# 1-Schematic_LoPoSwitch.net
KiCad netlist of a schematic drawn in EasyEDA
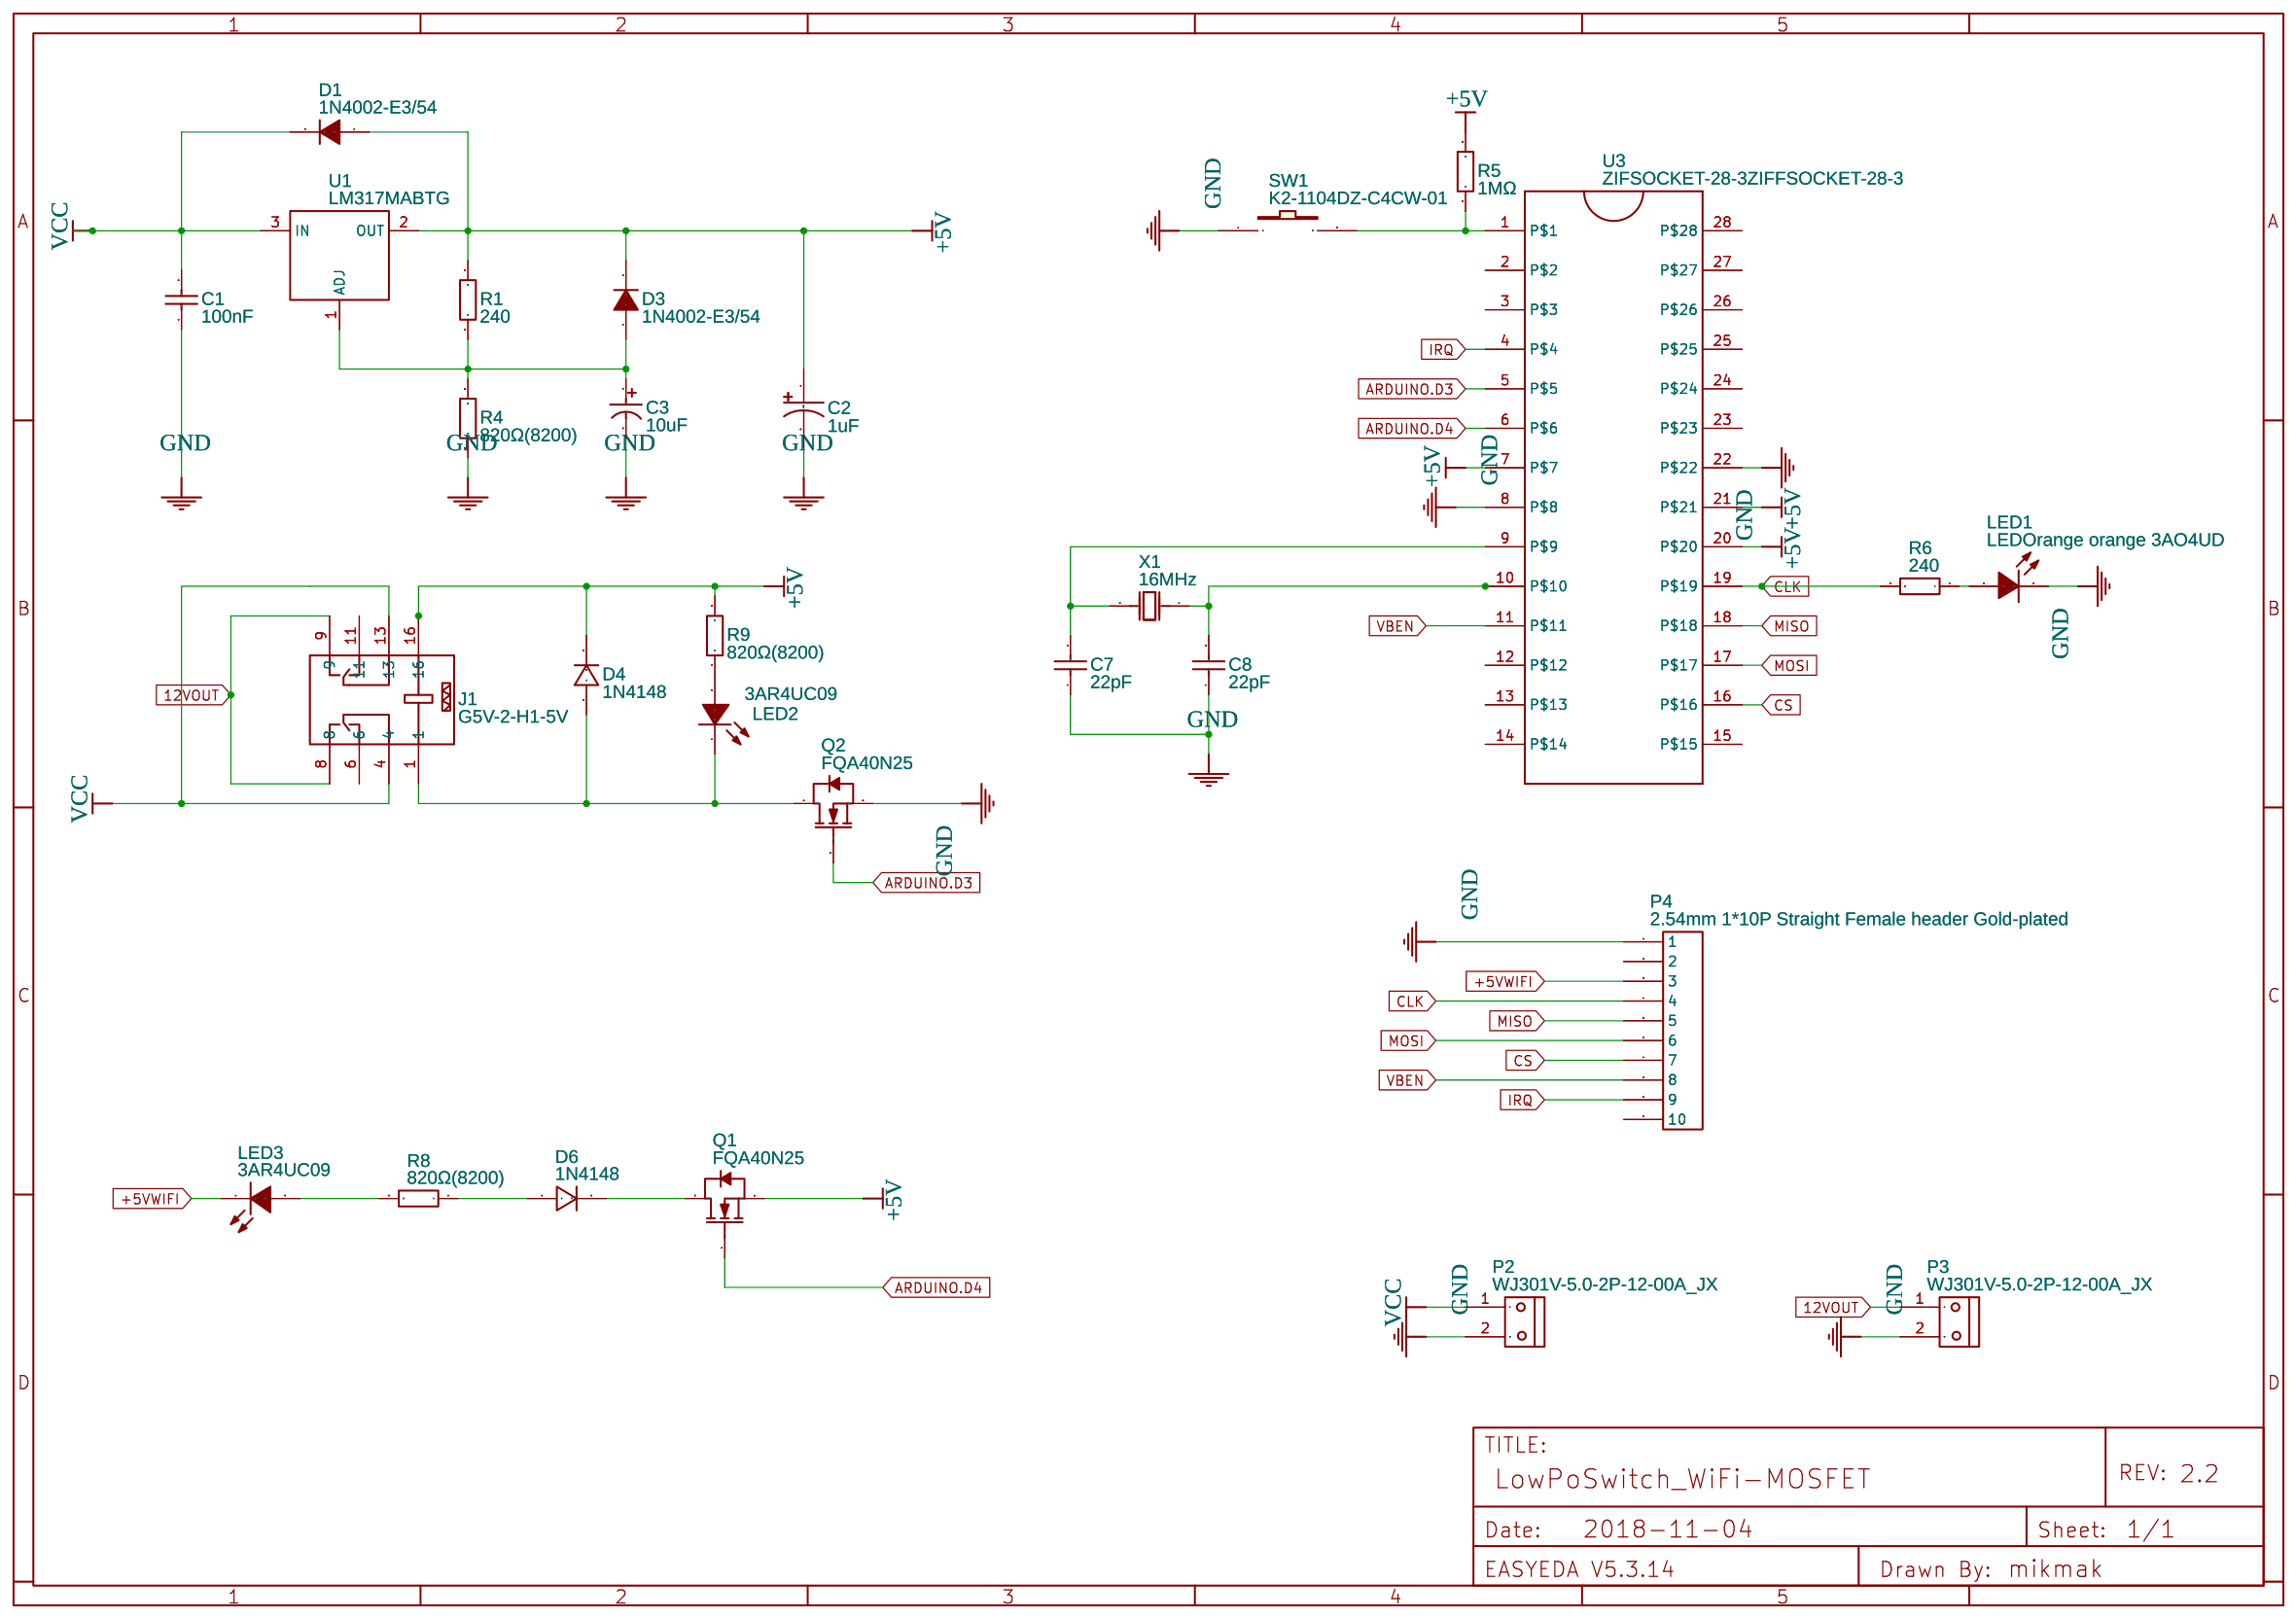
[diagram p0: schematic sheet]

(export (version "E")
  (design (tool "Eeschema 10.0.6"))
  (components
    (comp (ref "C1")
      (value "100nF")
      (fields
        (field (name "BOM_Manufacturer Part") "MPP104K5130508LC")
        (field (name "BOM_Supplier Part") "C109523")
      )
      (libsource (lib "") (part "MPP104K5130508LC"))
    )
    (comp (ref "C2")
      (value "1uF")
      (fields
        (field (name "BOM_Manufacturer Part") "T322A105K020AT")
        (field (name "BOM_Supplier Part") "C219517")
      )
      (libsource (lib "") (part "T322A105K020AT"))
    )
    (comp (ref "C3")
      (value "10uF")
      (fields (field (name "BOM_Manufacturer Part") "10uf/100V") (field (name "BOM_Supplier Part") "C2029"))
      (libsource (lib "") (part "10uf/100V"))
    )
    (comp (ref "C7")
      (value "22pF")
      (fields
        (field (name "BOM_Manufacturer Part") "Monolithic0603N220J500")
        (field (name "BOM_Supplier Part") "C110283")
      )
      (libsource (lib "") (part "Monolithic0603N220J500"))
    )
    (comp (ref "C8")
      (value "22pF")
      (fields
        (field (name "BOM_Manufacturer Part") "Monolithic0603N220J500")
        (field (name "BOM_Supplier Part") "C110283")
      )
      (libsource (lib "") (part "Monolithic0603N220J500"))
    )
    (comp (ref "D1")
      (value "1N4002-E3/54")
      (fields (field (name "BOM_Supplier Part") "C33504"))
      (libsource (lib "") (part "Unknown_160_60"))
    )
    (comp (ref "D3")
      (value "1N4002-E3/54")
      (fields (field (name "BOM_Supplier Part") "C33504"))
      (libsource (lib "") (part "Unknown_310_145"))
    )
    (comp (ref "D4")
      (value "1N4148")
      (fields (field (name "BOM_Supplier Part") "C163750"))
      (libsource (lib "") (part "Unknown_290_335"))
    )
    (comp (ref "D6")
      (value "1N4148")
      (fields (field (name "BOM_Supplier Part") "C163750"))
      (libsource (lib "") (part "Unknown_280_600"))
    )
    (comp (ref "J1")
      (value "G5V-2-H1-5V")
      (fields (field (name "BOM_Supplier Part") "C28066"))
      (libsource (lib "") (part "Unknown_185_340"))
    )
    (comp (ref "LED1")
      (value "LEDOrange orange 3AO4UD")
      (fields (field (name "BOM_Supplier Part") "C62095"))
      (libsource (lib "") (part "Unknown_1010_290"))
    )
    (comp (ref "LED2")
      (value "3AR4UC09")
      (fields (field (name "BOM_Supplier Part") "C6211"))
      (libsource (lib "") (part "Unknown_355_355"))
    )
    (comp (ref "LED3")
      (value "3AR4UC09")
      (fields (field (name "BOM_Supplier Part") "C6211"))
      (libsource (lib "") (part "Unknown_125_600"))
    )
    (comp (ref "P2")
      (value "WJ301V-5.0-2P-12-00A_JX")
      (fields (field (name "BOM_Manufacturer Part") "?") (field (name "BOM_Supplier Part") "C72326"))
      (libsource (lib "") (part "Unknown_755_655"))
    )
    (comp (ref "P3")
      (value "WJ301V-5.0-2P-12-00A_JX")
      (fields (field (name "BOM_Manufacturer Part") "?") (field (name "BOM_Supplier Part") "C72326"))
      (libsource (lib "") (part "Unknown_975_655"))
    )
    (comp (ref "P4")
      (value "2.54mm 1*10P Straight Female header Gold-plated")
      (fields (field (name "BOM_Supplier Part") "C35445"))
      (libsource (lib "") (part "Unknown_825_510"))
    )
    (comp (ref "Q1")
      (value "FQA40N25")
      (fields (field (name "BOM_Supplier Part") "C10877"))
      (libsource (lib "") (part "Unknown_360_610"))
    )
    (comp (ref "Q2")
      (value "FQA40N25")
      (fields (field (name "BOM_Supplier Part") "C10877"))
      (libsource (lib "") (part "Unknown_415_410"))
    )
    (comp (ref "R1")
      (value "240")
      (fields
        (field (name "BOM_Manufacturer Part") "MF1/8W-240Ω±1% T52")
        (field (name "BOM_Supplier Part") "C119165")
      )
      (libsource (lib "") (part "MF1/8W-240Ω±1% T52"))
    )
    (comp (ref "R4")
      (value "820Ω(8200)")
      (fields
        (field (name "BOM_Manufacturer Part") "MF1/8W-820Ω±1% T52")
        (field (name "BOM_Supplier Part") "C119177")
      )
      (libsource (lib "") (part "MF1/8W-820Ω±1% T52"))
    )
    (comp (ref "R5")
      (value "1MΩ")
      (fields
        (field (name "BOM_Manufacturer Part") "MFR0W4F1004A50")
        (field (name "BOM_Supplier Part") "C58596")
      )
      (libsource (lib "") (part "MFR0W4F1004A50"))
    )
    (comp (ref "R6")
      (value "240")
      (fields
        (field (name "BOM_Manufacturer Part") "MF1/8W-240Ω±1% T52")
        (field (name "BOM_Supplier Part") "C119165")
      )
      (libsource (lib "") (part "MF1/8W-240Ω±1% T52_1"))
    )
    (comp (ref "R8")
      (value "820Ω(8200)")
      (fields
        (field (name "BOM_Manufacturer Part") "MF1/8W-820Ω±1% T52")
        (field (name "BOM_Supplier Part") "C119177")
      )
      (libsource (lib "") (part "MF1/8W-820Ω±1% T52_1"))
    )
    (comp (ref "R9")
      (value "820Ω(8200)")
      (fields
        (field (name "BOM_Manufacturer Part") "MF1/8W-820Ω±1% T52")
        (field (name "BOM_Supplier Part") "C119177")
      )
      (libsource (lib "") (part "MF1/8W-820Ω±1% T52"))
    )
    (comp (ref "SW1")
      (value "K2-1104DZ-C4CW-01")
      (fields (field (name "BOM_Supplier Part") "C145889"))
      (libsource (lib "") (part "Unknown_640_110"))
    )
    (comp (ref "U1")
      (value "LM317MABTG")
      (fields (field (name "BOM_Supplier Part") "C94823"))
      (libsource (lib "") (part "Unknown_165_120"))
    )
    (comp (ref "U3")
      (value "ZIFSOCKET-28-3ZIFFSOCKET-28-3")
      (fields (field (name "BOM_Manufacturer Part") "?"))
      (libsource (lib "") (part "Unknown_765_390"))
    )
    (comp (ref "X1")
      (value "16MHz")
      (fields
        (field (name "BOM_Manufacturer Part") "X49SD16MSD2SC")
        (field (name "BOM_Supplier Part") "C16212")
      )
      (libsource (lib "") (part "X49SD16MSD2SC"))
    )
  )
  (nets
    (net (code "1") (name "+5V") (class "Default")
      (node (ref "C2") (pin "1") (pinfunction "1_1") (pintype "unspecified"))
      (node (ref "D1") (pin "1") (pinfunction "A_1") (pintype "unspecified"))
      (node (ref "D3") (pin "2") (pinfunction "K_2") (pintype "unspecified"))
      (node (ref "D4") (pin "2") (pinfunction "2_2") (pintype "unspecified"))
      (node (ref "J1") (pin "16") (pinfunction "16_16") (pintype "unspecified"))
      (node (ref "Q1") (pin "3") (pinfunction "S_3") (pintype "unspecified"))
      (node (ref "R1") (pin "2") (pinfunction "2_2") (pintype "input"))
      (node (ref "R5") (pin "2") (pinfunction "2_2") (pintype "input"))
      (node (ref "R9") (pin "2") (pinfunction "2_2") (pintype "input"))
      (node (ref "U1") (pin "2") (pinfunction "OUT_2") (pintype "unspecified"))
      (node (ref "U3") (pin "20") (pinfunction "P$20_20") (pintype "unspecified"))
      (node (ref "U3") (pin "21") (pinfunction "P$21_21") (pintype "unspecified"))
      (node (ref "U3") (pin "7") (pinfunction "P$7_7") (pintype "unspecified"))
    )
    (net (code "2") (name "+5VWIFI") (class "Default")
      (node (ref "LED3") (pin "1") (pinfunction "K_1") (pintype "unspecified"))
      (node (ref "P4") (pin "3") (pinfunction "3_3") (pintype "input"))
    )
    (net (code "3") (name "12VOUT") (class "Default")
      (node (ref "J1") (pin "8") (pinfunction "8_8") (pintype "unspecified"))
      (node (ref "J1") (pin "9") (pinfunction "9_9") (pintype "unspecified"))
      (node (ref "P3") (pin "1") (pinfunction "1_1") (pintype "unspecified"))
    )
    (net (code "4") (name "ARDUINO.D3") (class "Default")
      (node (ref "Q2") (pin "1") (pinfunction "G_1") (pintype "unspecified"))
      (node (ref "U3") (pin "5") (pinfunction "P$5_5") (pintype "unspecified"))
    )
    (net (code "5") (name "ARDUINO.D4") (class "Default")
      (node (ref "Q1") (pin "1") (pinfunction "G_1") (pintype "unspecified"))
      (node (ref "U3") (pin "6") (pinfunction "P$6_6") (pintype "unspecified"))
    )
    (net (code "6") (name "CLK") (class "Default")
      (node (ref "P4") (pin "4") (pinfunction "4_4") (pintype "input"))
      (node (ref "R6") (pin "2") (pinfunction "2_2") (pintype "input"))
      (node (ref "U3") (pin "19") (pinfunction "P$19_19") (pintype "unspecified"))
    )
    (net (code "7") (name "CS") (class "Default")
      (node (ref "P4") (pin "7") (pinfunction "7_7") (pintype "input"))
      (node (ref "U3") (pin "16") (pinfunction "P$16_16") (pintype "unspecified"))
    )
    (net (code "8") (name "GND") (class "Default")
      (node (ref "C1") (pin "1") (pinfunction "1_1") (pintype "input"))
      (node (ref "C2") (pin "2") (pinfunction "2_2") (pintype "unspecified"))
      (node (ref "C3") (pin "2") (pinfunction "2_2") (pintype "input"))
      (node (ref "C7") (pin "1") (pinfunction "1_1") (pintype "input"))
      (node (ref "C8") (pin "1") (pinfunction "1_1") (pintype "input"))
      (node (ref "LED1") (pin "1") (pinfunction "K_1") (pintype "unspecified"))
      (node (ref "P2") (pin "2") (pinfunction "2_2") (pintype "unspecified"))
      (node (ref "P3") (pin "2") (pinfunction "2_2") (pintype "unspecified"))
      (node (ref "P4") (pin "1") (pinfunction "1_1") (pintype "input"))
      (node (ref "Q2") (pin "3") (pinfunction "S_3") (pintype "unspecified"))
      (node (ref "R4") (pin "1") (pinfunction "1_1") (pintype "input"))
      (node (ref "SW1") (pin "1") (pinfunction "1_1") (pintype "input"))
      (node (ref "U3") (pin "22") (pinfunction "P$22_22") (pintype "unspecified"))
      (node (ref "U3") (pin "8") (pinfunction "P$8_8") (pintype "unspecified"))
    )
    (net (code "9") (name "IRQ") (class "Default")
      (node (ref "P4") (pin "9") (pinfunction "9_9") (pintype "input"))
      (node (ref "U3") (pin "4") (pinfunction "P$4_4") (pintype "unspecified"))
    )
    (net (code "10") (name "MISO") (class "Default")
      (node (ref "P4") (pin "5") (pinfunction "5_5") (pintype "input"))
      (node (ref "U3") (pin "18") (pinfunction "P$18_18") (pintype "unspecified"))
    )
    (net (code "11") (name "MOSI") (class "Default")
      (node (ref "P4") (pin "6") (pinfunction "6_6") (pintype "input"))
      (node (ref "U3") (pin "17") (pinfunction "P$17_17") (pintype "unspecified"))
    )
    (net (code "12") (name "Net-(D3-A)") (class "Default")
      (node (ref "C3") (pin "1") (pinfunction "1_1") (pintype "input"))
      (node (ref "D3") (pin "1") (pinfunction "A_1") (pintype "unspecified"))
      (node (ref "R1") (pin "1") (pinfunction "1_1") (pintype "input"))
      (node (ref "R4") (pin "2") (pinfunction "2_2") (pintype "input"))
      (node (ref "U1") (pin "1") (pinfunction "ADJ_1") (pintype "input"))
    )
    (net (code "13") (name "Net-(D6-Pad1)") (class "Default")
      (node (ref "D6") (pin "1") (pinfunction "1_1") (pintype "unspecified"))
      (node (ref "R8") (pin "1") (pinfunction "1_1") (pintype "input"))
    )
    (net (code "14") (name "Net-(LED1-A)") (class "Default")
      (node (ref "LED1") (pin "2") (pinfunction "A_2") (pintype "unspecified"))
      (node (ref "R6") (pin "1") (pinfunction "1_1") (pintype "input"))
    )
    (net (code "15") (name "Net-(LED2-A)") (class "Default")
      (node (ref "LED2") (pin "2") (pinfunction "A_2") (pintype "unspecified"))
      (node (ref "R9") (pin "1") (pinfunction "1_1") (pintype "input"))
    )
    (net (code "16") (name "Net-(LED2-K)") (class "Default")
      (node (ref "D4") (pin "1") (pinfunction "1_1") (pintype "unspecified"))
      (node (ref "J1") (pin "1") (pinfunction "1_1") (pintype "unspecified"))
      (node (ref "LED2") (pin "1") (pinfunction "K_1") (pintype "unspecified"))
      (node (ref "Q2") (pin "2") (pinfunction "D_2") (pintype "unspecified"))
    )
    (net (code "17") (name "Net-(LED3-A)") (class "Default")
      (node (ref "LED3") (pin "2") (pinfunction "A_2") (pintype "unspecified"))
      (node (ref "R8") (pin "2") (pinfunction "2_2") (pintype "input"))
    )
    (net (code "18") (name "Net-(Q1-D)") (class "Default")
      (node (ref "D6") (pin "2") (pinfunction "2_2") (pintype "unspecified"))
      (node (ref "Q1") (pin "2") (pinfunction "D_2") (pintype "unspecified"))
    )
    (net (code "19") (name "Net-(U3-P$1)") (class "Default")
      (node (ref "R5") (pin "1") (pinfunction "1_1") (pintype "input"))
      (node (ref "SW1") (pin "2") (pinfunction "2_2") (pintype "input"))
      (node (ref "U3") (pin "1") (pinfunction "P$1_1") (pintype "unspecified"))
    )
    (net (code "20") (name "Net-(U3-P$9)") (class "Default")
      (node (ref "C7") (pin "2") (pinfunction "2_2") (pintype "input"))
      (node (ref "U3") (pin "9") (pinfunction "P$9_9") (pintype "unspecified"))
      (node (ref "X1") (pin "2") (pinfunction "OSC2_2") (pintype "input"))
    )
    (net (code "21") (name "Net-(U3-P$10)") (class "Default")
      (node (ref "C8") (pin "2") (pinfunction "2_2") (pintype "input"))
      (node (ref "U3") (pin "10") (pinfunction "P$10_10") (pintype "unspecified"))
      (node (ref "X1") (pin "1") (pinfunction "OSC1_1") (pintype "input"))
    )
    (net (code "22") (name "VBEN") (class "Default")
      (node (ref "P4") (pin "8") (pinfunction "8_8") (pintype "input"))
      (node (ref "U3") (pin "11") (pinfunction "P$11_11") (pintype "unspecified"))
    )
    (net (code "23") (name "VCC") (class "Default")
      (node (ref "C1") (pin "2") (pinfunction "2_2") (pintype "input"))
      (node (ref "D1") (pin "2") (pinfunction "K_2") (pintype "unspecified"))
      (node (ref "J1") (pin "13") (pinfunction "13_13") (pintype "unspecified"))
      (node (ref "J1") (pin "4") (pinfunction "4_4") (pintype "unspecified"))
      (node (ref "P2") (pin "1") (pinfunction "1_1") (pintype "unspecified"))
      (node (ref "U1") (pin "3") (pinfunction "IN_3") (pintype "input"))
    )
    (net (code "24") (name "unconnected-(J1-Pad6)") (class "Default")
      (node (ref "J1") (pin "6") (pinfunction "6_6") (pintype "unspecified"))
    )
    (net (code "25") (name "unconnected-(J1-Pad11)") (class "Default")
      (node (ref "J1") (pin "11") (pinfunction "11_11") (pintype "unspecified"))
    )
    (net (code "26") (name "unconnected-(P4-Pad2)") (class "Default")
      (node (ref "P4") (pin "2") (pinfunction "2_2") (pintype "input"))
    )
    (net (code "27") (name "unconnected-(P4-Pad10)") (class "Default")
      (node (ref "P4") (pin "10") (pinfunction "10_10") (pintype "input"))
    )
    (net (code "28") (name "unconnected-(U3-P$2-Pad2)") (class "Default")
      (node (ref "U3") (pin "2") (pinfunction "P$2_2") (pintype "unspecified"))
    )
    (net (code "29") (name "unconnected-(U3-P$3-Pad3)") (class "Default")
      (node (ref "U3") (pin "3") (pinfunction "P$3_3") (pintype "unspecified"))
    )
    (net (code "30") (name "unconnected-(U3-P$12-Pad12)") (class "Default")
      (node (ref "U3") (pin "12") (pinfunction "P$12_12") (pintype "unspecified"))
    )
    (net (code "31") (name "unconnected-(U3-P$13-Pad13)") (class "Default")
      (node (ref "U3") (pin "13") (pinfunction "P$13_13") (pintype "unspecified"))
    )
    (net (code "32") (name "unconnected-(U3-P$14-Pad14)") (class "Default")
      (node (ref "U3") (pin "14") (pinfunction "P$14_14") (pintype "unspecified"))
    )
    (net (code "33") (name "unconnected-(U3-P$15-Pad15)") (class "Default")
      (node (ref "U3") (pin "15") (pinfunction "P$15_15") (pintype "unspecified"))
    )
    (net (code "34") (name "unconnected-(U3-P$23-Pad23)") (class "Default")
      (node (ref "U3") (pin "23") (pinfunction "P$23_23") (pintype "unspecified"))
    )
    (net (code "35") (name "unconnected-(U3-P$24-Pad24)") (class "Default")
      (node (ref "U3") (pin "24") (pinfunction "P$24_24") (pintype "unspecified"))
    )
    (net (code "36") (name "unconnected-(U3-P$25-Pad25)") (class "Default")
      (node (ref "U3") (pin "25") (pinfunction "P$25_25") (pintype "unspecified"))
    )
    (net (code "37") (name "unconnected-(U3-P$26-Pad26)") (class "Default")
      (node (ref "U3") (pin "26") (pinfunction "P$26_26") (pintype "unspecified"))
    )
    (net (code "38") (name "unconnected-(U3-P$27-Pad27)") (class "Default")
      (node (ref "U3") (pin "27") (pinfunction "P$27_27") (pintype "unspecified"))
    )
    (net (code "39") (name "unconnected-(U3-P$28-Pad28)") (class "Default")
      (node (ref "U3") (pin "28") (pinfunction "P$28_28") (pintype "unspecified"))
    )
  )
)
